# amp-7.net
KiCad netlist of a schematic drawn in EAGLE
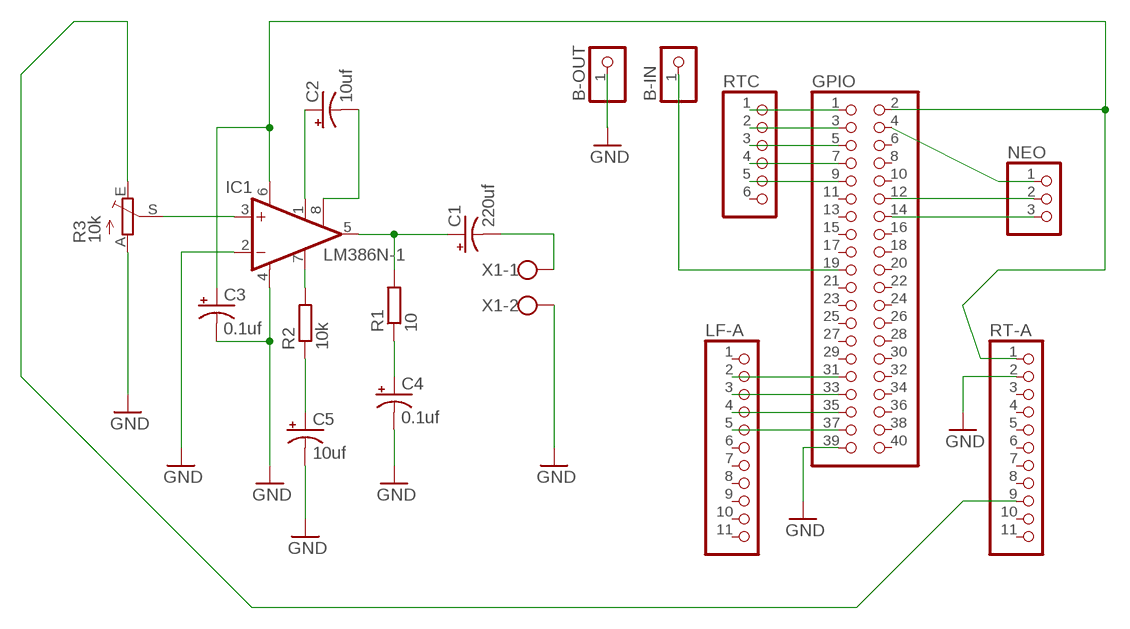
[diagram p0: schematic, sheet 1]

(export (version "E")
  (design (tool "Eeschema 10.0.6"))
  (components
    (comp (ref "B-IN")
      (value "PINHD-1X1")
      (footprint "eagle-import:1X01")
      (libsource (lib "eagle-import") (part "PINHD-1X1"))
    )
    (comp (ref "B-OUT")
      (value "PINHD-1X1")
      (footprint "eagle-import:1X01")
      (libsource (lib "eagle-import") (part "PINHD-1X1"))
    )
    (comp (ref "C1")
      (value "220uf")
      (footprint "eagle-import:E2-5")
      (libsource (lib "eagle-import") (part "CPOL-USE2-5"))
    )
    (comp (ref "C2")
      (value "10uf")
      (footprint "eagle-import:E2-4")
      (libsource (lib "eagle-import") (part "CPOL-USE2-4"))
    )
    (comp (ref "C3")
      (value "0.1uf")
      (footprint "eagle-import:E2-4")
      (libsource (lib "eagle-import") (part "CPOL-USE2-4"))
    )
    (comp (ref "C4")
      (value "0.1uf")
      (footprint "eagle-import:E2-4")
      (libsource (lib "eagle-import") (part "CPOL-USE2-4"))
    )
    (comp (ref "C5")
      (value "10uf")
      (footprint "eagle-import:E2-4")
      (libsource (lib "eagle-import") (part "CPOL-USE2-4"))
    )
    (comp (ref "GPIO")
      (value "PINHD-2X20")
      (footprint "eagle-import:2X20")
      (libsource (lib "eagle-import") (part "PINHD-2X20"))
    )
    (comp (ref "IC1")
      (value "LM386N-1")
      (footprint "eagle-import:DIL08")
      (libsource (lib "eagle-import") (part "LM386?-N1"))
    )
    (comp (ref "LF-A")
      (value "HEADER-1X1176MIL")
      (footprint "eagle-import:1X11_ROUND_76")
      (libsource (lib "eagle-import") (part "HEADER-1X1176MIL"))
    )
    (comp (ref "NEO")
      (value "PINHD-1X3")
      (footprint "eagle-import:1X03")
      (libsource (lib "eagle-import") (part "PINHD-1X3"))
    )
    (comp (ref "R1")
      (value "10")
      (footprint "eagle-import:0204_7")
      (libsource (lib "eagle-import") (part "R0204/7"))
    )
    (comp (ref "R2")
      (value "10k")
      (footprint "eagle-import:0204_7")
      (libsource (lib "eagle-import") (part "R0204/7"))
    )
    (comp (ref "R3")
      (value "10k")
      (footprint "eagle-import:LI10")
      (libsource (lib "eagle-import") (part "TRIM_EU-LI10"))
    )
    (comp (ref "RT-A")
      (value "HEADER-1X1176MIL")
      (footprint "eagle-import:1X11_ROUND_76")
      (libsource (lib "eagle-import") (part "HEADER-1X1176MIL"))
    )
    (comp (ref "RTC")
      (value "PINHD-1X6")
      (footprint "eagle-import:1X06")
      (libsource (lib "eagle-import") (part "PINHD-1X6"))
    )
    (comp (ref "X1")
      (value "W237-102")
      (footprint "eagle-import:W237-102")
      (fields (field (name "MPN") "237-102"))
      (libsource (lib "eagle-import") (part "W237-102"))
    )
  )
  (nets
    (net (code "1") (name "GND") (class "Default")
      (node (ref "B-OUT") (pin "1") (pinfunction "1_1") (pintype "passive"))
      (node (ref "C3") (pin "-") (pinfunction "-_-") (pintype "passive"))
      (node (ref "C4") (pin "-") (pinfunction "-_-") (pintype "passive"))
      (node (ref "C5") (pin "-") (pinfunction "-_-") (pintype "passive"))
      (node (ref "GPIO") (pin "39") (pinfunction "39_39") (pintype "passive"))
      (node (ref "IC1") (pin "2") (pinfunction "-IN_2") (pintype "input"))
      (node (ref "IC1") (pin "4") (pinfunction "GND_4") (pintype "power_in"))
      (node (ref "R3") (pin "A") (pinfunction "A_A") (pintype "passive"))
      (node (ref "RT-A") (pin "2") (pinfunction "2_2") (pintype "passive"))
      (node (ref "X1") (pin "2") (pinfunction "KL_2") (pintype "passive"))
    )
    (net (code "2") (name "Net-(B-IN-Pad1)") (class "Default")
      (node (ref "B-IN") (pin "1") (pinfunction "1_1") (pintype "passive"))
      (node (ref "GPIO") (pin "19") (pinfunction "19_19") (pintype "passive"))
    )
    (net (code "3") (name "Net-(C2-Pad+)") (class "Default")
      (node (ref "C2") (pin "+") (pinfunction "+_+") (pintype "passive"))
      (node (ref "IC1") (pin "1") (pinfunction "GAIN_1") (pintype "passive"))
    )
    (net (code "4") (name "Net-(C2-Pad-)") (class "Default")
      (node (ref "C2") (pin "-") (pinfunction "-_-") (pintype "passive"))
      (node (ref "IC1") (pin "8") (pinfunction "GAIN_8") (pintype "passive"))
    )
    (net (code "5") (name "Net-(C4-Pad+)") (class "Default")
      (node (ref "C4") (pin "+") (pinfunction "+_+") (pintype "passive"))
      (node (ref "R1") (pin "1") (pinfunction "1_1") (pintype "passive"))
    )
    (net (code "6") (name "Net-(C5-Pad+)") (class "Default")
      (node (ref "C5") (pin "+") (pinfunction "+_+") (pintype "passive"))
      (node (ref "R2") (pin "1") (pinfunction "1_1") (pintype "passive"))
    )
    (net (code "7") (name "Net-(GPIO-Pad1)") (class "Default")
      (node (ref "GPIO") (pin "1") (pinfunction "1_1") (pintype "passive"))
      (node (ref "RTC") (pin "1") (pinfunction "1_1") (pintype "passive"))
    )
    (net (code "8") (name "Net-(GPIO-Pad3)") (class "Default")
      (node (ref "GPIO") (pin "3") (pinfunction "3_3") (pintype "passive"))
      (node (ref "RTC") (pin "2") (pinfunction "2_2") (pintype "passive"))
    )
    (net (code "9") (name "Net-(GPIO-Pad4)") (class "Default")
      (node (ref "GPIO") (pin "4") (pinfunction "4_4") (pintype "passive"))
      (node (ref "NEO") (pin "1") (pinfunction "1_1") (pintype "passive"))
    )
    (net (code "10") (name "Net-(GPIO-Pad5)") (class "Default")
      (node (ref "GPIO") (pin "5") (pinfunction "5_5") (pintype "passive"))
      (node (ref "RTC") (pin "3") (pinfunction "3_3") (pintype "passive"))
    )
    (net (code "11") (name "Net-(GPIO-Pad7)") (class "Default")
      (node (ref "GPIO") (pin "7") (pinfunction "7_7") (pintype "passive"))
      (node (ref "RTC") (pin "4") (pinfunction "4_4") (pintype "passive"))
    )
    (net (code "12") (name "Net-(GPIO-Pad9)") (class "Default")
      (node (ref "GPIO") (pin "9") (pinfunction "9_9") (pintype "passive"))
      (node (ref "RTC") (pin "5") (pinfunction "5_5") (pintype "passive"))
    )
    (net (code "13") (name "Net-(GPIO-Pad12)") (class "Default")
      (node (ref "GPIO") (pin "12") (pinfunction "12_12") (pintype "passive"))
      (node (ref "NEO") (pin "2") (pinfunction "2_2") (pintype "passive"))
    )
    (net (code "14") (name "Net-(GPIO-Pad14)") (class "Default")
      (node (ref "GPIO") (pin "14") (pinfunction "14_14") (pintype "passive"))
      (node (ref "NEO") (pin "3") (pinfunction "3_3") (pintype "passive"))
    )
    (net (code "15") (name "Net-(GPIO-Pad31)") (class "Default")
      (node (ref "GPIO") (pin "31") (pinfunction "31_31") (pintype "passive"))
      (node (ref "LF-A") (pin "2") (pinfunction "2_2") (pintype "passive"))
    )
    (net (code "16") (name "Net-(GPIO-Pad33)") (class "Default")
      (node (ref "GPIO") (pin "33") (pinfunction "33_33") (pintype "passive"))
      (node (ref "LF-A") (pin "3") (pinfunction "3_3") (pintype "passive"))
    )
    (net (code "17") (name "Net-(GPIO-Pad35)") (class "Default")
      (node (ref "GPIO") (pin "35") (pinfunction "35_35") (pintype "passive"))
      (node (ref "LF-A") (pin "4") (pinfunction "4_4") (pintype "passive"))
    )
    (net (code "18") (name "Net-(GPIO-Pad37)") (class "Default")
      (node (ref "GPIO") (pin "37") (pinfunction "37_37") (pintype "passive"))
      (node (ref "LF-A") (pin "5") (pinfunction "5_5") (pintype "passive"))
    )
    (net (code "19") (name "Net-(IC1-+IN)") (class "Default")
      (node (ref "IC1") (pin "3") (pinfunction "+IN_3") (pintype "input"))
      (node (ref "R3") (pin "S") (pinfunction "S_S") (pintype "passive"))
    )
    (net (code "20") (name "Net-(IC1-BYPASS)") (class "Default")
      (node (ref "IC1") (pin "7") (pinfunction "BYPASS_7") (pintype "passive"))
      (node (ref "R2") (pin "2") (pinfunction "2_2") (pintype "passive"))
    )
    (net (code "21") (name "Net-(IC1-OUT)") (class "Default")
      (node (ref "C1") (pin "+") (pinfunction "+_+") (pintype "passive"))
      (node (ref "IC1") (pin "5") (pinfunction "OUT_5") (pintype "output"))
      (node (ref "R1") (pin "2") (pinfunction "2_2") (pintype "passive"))
    )
    (net (code "22") (name "Net-(IC1-VS)") (class "Default")
      (node (ref "C3") (pin "+") (pinfunction "+_+") (pintype "passive"))
      (node (ref "GPIO") (pin "2") (pinfunction "2_2") (pintype "passive"))
      (node (ref "IC1") (pin "6") (pinfunction "VS_6") (pintype "power_in"))
      (node (ref "RT-A") (pin "1") (pinfunction "1_1") (pintype "passive"))
    )
    (net (code "23") (name "Net-(R3-PadE)") (class "Default")
      (node (ref "R3") (pin "E") (pinfunction "E_E") (pintype "passive"))
      (node (ref "RT-A") (pin "9") (pinfunction "9_9") (pintype "passive"))
    )
    (net (code "24") (name "Net-(X1A-KL)") (class "Default")
      (node (ref "C1") (pin "-") (pinfunction "-_-") (pintype "passive"))
      (node (ref "X1") (pin "1") (pinfunction "KL_1") (pintype "passive"))
    )
    (net (code "25") (name "unconnected-(GPIO-Pad6)") (class "Default")
      (node (ref "GPIO") (pin "6") (pinfunction "6_6") (pintype "passive"))
    )
    (net (code "26") (name "unconnected-(GPIO-Pad8)") (class "Default")
      (node (ref "GPIO") (pin "8") (pinfunction "8_8") (pintype "passive"))
    )
    (net (code "27") (name "unconnected-(GPIO-Pad10)") (class "Default")
      (node (ref "GPIO") (pin "10") (pinfunction "10_10") (pintype "passive"))
    )
    (net (code "28") (name "unconnected-(GPIO-Pad11)") (class "Default")
      (node (ref "GPIO") (pin "11") (pinfunction "11_11") (pintype "passive"))
    )
    (net (code "29") (name "unconnected-(GPIO-Pad13)") (class "Default")
      (node (ref "GPIO") (pin "13") (pinfunction "13_13") (pintype "passive"))
    )
    (net (code "30") (name "unconnected-(GPIO-Pad15)") (class "Default")
      (node (ref "GPIO") (pin "15") (pinfunction "15_15") (pintype "passive"))
    )
    (net (code "31") (name "unconnected-(GPIO-Pad16)") (class "Default")
      (node (ref "GPIO") (pin "16") (pinfunction "16_16") (pintype "passive"))
    )
    (net (code "32") (name "unconnected-(GPIO-Pad17)") (class "Default")
      (node (ref "GPIO") (pin "17") (pinfunction "17_17") (pintype "passive"))
    )
    (net (code "33") (name "unconnected-(GPIO-Pad18)") (class "Default")
      (node (ref "GPIO") (pin "18") (pinfunction "18_18") (pintype "passive"))
    )
    (net (code "34") (name "unconnected-(GPIO-Pad20)") (class "Default")
      (node (ref "GPIO") (pin "20") (pinfunction "20_20") (pintype "passive"))
    )
    (net (code "35") (name "unconnected-(GPIO-Pad21)") (class "Default")
      (node (ref "GPIO") (pin "21") (pinfunction "21_21") (pintype "passive"))
    )
    (net (code "36") (name "unconnected-(GPIO-Pad22)") (class "Default")
      (node (ref "GPIO") (pin "22") (pinfunction "22_22") (pintype "passive"))
    )
    (net (code "37") (name "unconnected-(GPIO-Pad23)") (class "Default")
      (node (ref "GPIO") (pin "23") (pinfunction "23_23") (pintype "passive"))
    )
    (net (code "38") (name "unconnected-(GPIO-Pad24)") (class "Default")
      (node (ref "GPIO") (pin "24") (pinfunction "24_24") (pintype "passive"))
    )
    (net (code "39") (name "unconnected-(GPIO-Pad25)") (class "Default")
      (node (ref "GPIO") (pin "25") (pinfunction "25_25") (pintype "passive"))
    )
    (net (code "40") (name "unconnected-(GPIO-Pad26)") (class "Default")
      (node (ref "GPIO") (pin "26") (pinfunction "26_26") (pintype "passive"))
    )
    (net (code "41") (name "unconnected-(GPIO-Pad27)") (class "Default")
      (node (ref "GPIO") (pin "27") (pinfunction "27_27") (pintype "passive"))
    )
    (net (code "42") (name "unconnected-(GPIO-Pad28)") (class "Default")
      (node (ref "GPIO") (pin "28") (pinfunction "28_28") (pintype "passive"))
    )
    (net (code "43") (name "unconnected-(GPIO-Pad29)") (class "Default")
      (node (ref "GPIO") (pin "29") (pinfunction "29_29") (pintype "passive"))
    )
    (net (code "44") (name "unconnected-(GPIO-Pad30)") (class "Default")
      (node (ref "GPIO") (pin "30") (pinfunction "30_30") (pintype "passive"))
    )
    (net (code "45") (name "unconnected-(GPIO-Pad32)") (class "Default")
      (node (ref "GPIO") (pin "32") (pinfunction "32_32") (pintype "passive"))
    )
    (net (code "46") (name "unconnected-(GPIO-Pad34)") (class "Default")
      (node (ref "GPIO") (pin "34") (pinfunction "34_34") (pintype "passive"))
    )
    (net (code "47") (name "unconnected-(GPIO-Pad36)") (class "Default")
      (node (ref "GPIO") (pin "36") (pinfunction "36_36") (pintype "passive"))
    )
    (net (code "48") (name "unconnected-(GPIO-Pad38)") (class "Default")
      (node (ref "GPIO") (pin "38") (pinfunction "38_38") (pintype "passive"))
    )
    (net (code "49") (name "unconnected-(GPIO-Pad40)") (class "Default")
      (node (ref "GPIO") (pin "40") (pinfunction "40_40") (pintype "passive"))
    )
    (net (code "50") (name "unconnected-(LF-A-Pad1)") (class "Default")
      (node (ref "LF-A") (pin "1") (pinfunction "1_1") (pintype "passive"))
    )
    (net (code "51") (name "unconnected-(LF-A-Pad6)") (class "Default")
      (node (ref "LF-A") (pin "6") (pinfunction "6_6") (pintype "passive"))
    )
    (net (code "52") (name "unconnected-(LF-A-Pad7)") (class "Default")
      (node (ref "LF-A") (pin "7") (pinfunction "7_7") (pintype "passive"))
    )
    (net (code "53") (name "unconnected-(LF-A-Pad8)") (class "Default")
      (node (ref "LF-A") (pin "8") (pinfunction "8_8") (pintype "passive"))
    )
    (net (code "54") (name "unconnected-(LF-A-Pad9)") (class "Default")
      (node (ref "LF-A") (pin "9") (pinfunction "9_9") (pintype "passive"))
    )
    (net (code "55") (name "unconnected-(LF-A-Pad10)") (class "Default")
      (node (ref "LF-A") (pin "10") (pinfunction "10_10") (pintype "passive"))
    )
    (net (code "56") (name "unconnected-(LF-A-Pad11)") (class "Default")
      (node (ref "LF-A") (pin "11") (pinfunction "11_11") (pintype "passive"))
    )
    (net (code "57") (name "unconnected-(RT-A-Pad3)") (class "Default")
      (node (ref "RT-A") (pin "3") (pinfunction "3_3") (pintype "passive"))
    )
    (net (code "58") (name "unconnected-(RT-A-Pad4)") (class "Default")
      (node (ref "RT-A") (pin "4") (pinfunction "4_4") (pintype "passive"))
    )
    (net (code "59") (name "unconnected-(RT-A-Pad5)") (class "Default")
      (node (ref "RT-A") (pin "5") (pinfunction "5_5") (pintype "passive"))
    )
    (net (code "60") (name "unconnected-(RT-A-Pad6)") (class "Default")
      (node (ref "RT-A") (pin "6") (pinfunction "6_6") (pintype "passive"))
    )
    (net (code "61") (name "unconnected-(RT-A-Pad7)") (class "Default")
      (node (ref "RT-A") (pin "7") (pinfunction "7_7") (pintype "passive"))
    )
    (net (code "62") (name "unconnected-(RT-A-Pad8)") (class "Default")
      (node (ref "RT-A") (pin "8") (pinfunction "8_8") (pintype "passive"))
    )
    (net (code "63") (name "unconnected-(RT-A-Pad10)") (class "Default")
      (node (ref "RT-A") (pin "10") (pinfunction "10_10") (pintype "passive"))
    )
    (net (code "64") (name "unconnected-(RT-A-Pad11)") (class "Default")
      (node (ref "RT-A") (pin "11") (pinfunction "11_11") (pintype "passive"))
    )
    (net (code "65") (name "unconnected-(RTC-Pad6)") (class "Default")
      (node (ref "RTC") (pin "6") (pinfunction "6_6") (pintype "passive"))
    )
  )
)
